# rosalina_new.net
KiCad netlist of a schematic drawn in EAGLE
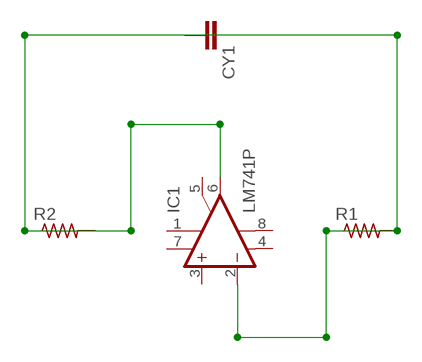
[diagram p0: schematic, sheet 1]

(export (version "E")
  (design (tool "Eeschema 10.0.6"))
  (components
    (comp (ref "CY1")
      (value "CYYC7B5")
      (footprint "eagle-import:YC7B5")
      (libsource (lib "eagle-import") (part "CYYC7B5"))
    )
    (comp (ref "IC1")
      (value "LM741P")
      (footprint "eagle-import:DIL08")
      (libsource (lib "eagle-import") (part "741PLM"))
    )
    (comp (ref "R1")
      (value "R-US_0204/7")
      (footprint "eagle-import:0204_7")
      (libsource (lib "eagle-import") (part "R-US_0204/7"))
    )
    (comp (ref "R2")
      (value "R-US_0204/7")
      (footprint "eagle-import:0204_7")
      (libsource (lib "eagle-import") (part "R-US_0204/7"))
    )
  )
  (nets
    (net (code "1") (name "/V+") (class "Default")
      (node (ref "IC1") (pin "7") (pinfunction "V+_7") (pintype "power_in"))
    )
    (net (code "2") (name "/V-") (class "Default")
      (node (ref "IC1") (pin "4") (pinfunction "V-_4") (pintype "power_in"))
    )
    (net (code "3") (name "Net-(IC1--IN)") (class "Default")
      (node (ref "IC1") (pin "2") (pinfunction "-IN_2") (pintype "input"))
      (node (ref "IC1") (pin "6") (pinfunction "OUT_6") (pintype "output"))
      (node (ref "R1") (pin "1") (pinfunction "1_1") (pintype "passive"))
      (node (ref "R1") (pin "2") (pinfunction "2_2") (pintype "passive"))
      (node (ref "R2") (pin "1") (pinfunction "1_1") (pintype "passive"))
    )
    (net (code "4") (name "unconnected-(CY1-Pad1)") (class "Default")
      (node (ref "CY1") (pin "1") (pinfunction "1_1") (pintype "passive"))
    )
    (net (code "5") (name "unconnected-(CY1-Pad2)") (class "Default")
      (node (ref "CY1") (pin "2") (pinfunction "2_2") (pintype "passive"))
    )
    (net (code "6") (name "unconnected-(IC1-+IN-Pad3)") (class "Default")
      (node (ref "IC1") (pin "3") (pinfunction "+IN_3") (pintype "input"))
    )
    (net (code "7") (name "unconnected-(IC1-ON1-Pad1)") (class "Default")
      (node (ref "IC1") (pin "1") (pinfunction "ON1_1") (pintype "passive"))
    )
    (net (code "8") (name "unconnected-(IC1-ON2-Pad5)") (class "Default")
      (node (ref "IC1") (pin "5") (pinfunction "ON2_5") (pintype "passive"))
    )
    (net (code "9") (name "unconnected-(IC1-OPT-Pad8)") (class "Default")
      (node (ref "IC1") (pin "8") (pinfunction "OPT_8") (pintype "passive"))
    )
    (net (code "10") (name "unconnected-(R2-Pad2)") (class "Default")
      (node (ref "R2") (pin "2") (pinfunction "2_2") (pintype "passive"))
    )
  )
)
